# tritiled22_cr2354_xpe_reverse.net
KiCad netlist of a schematic drawn in EAGLE
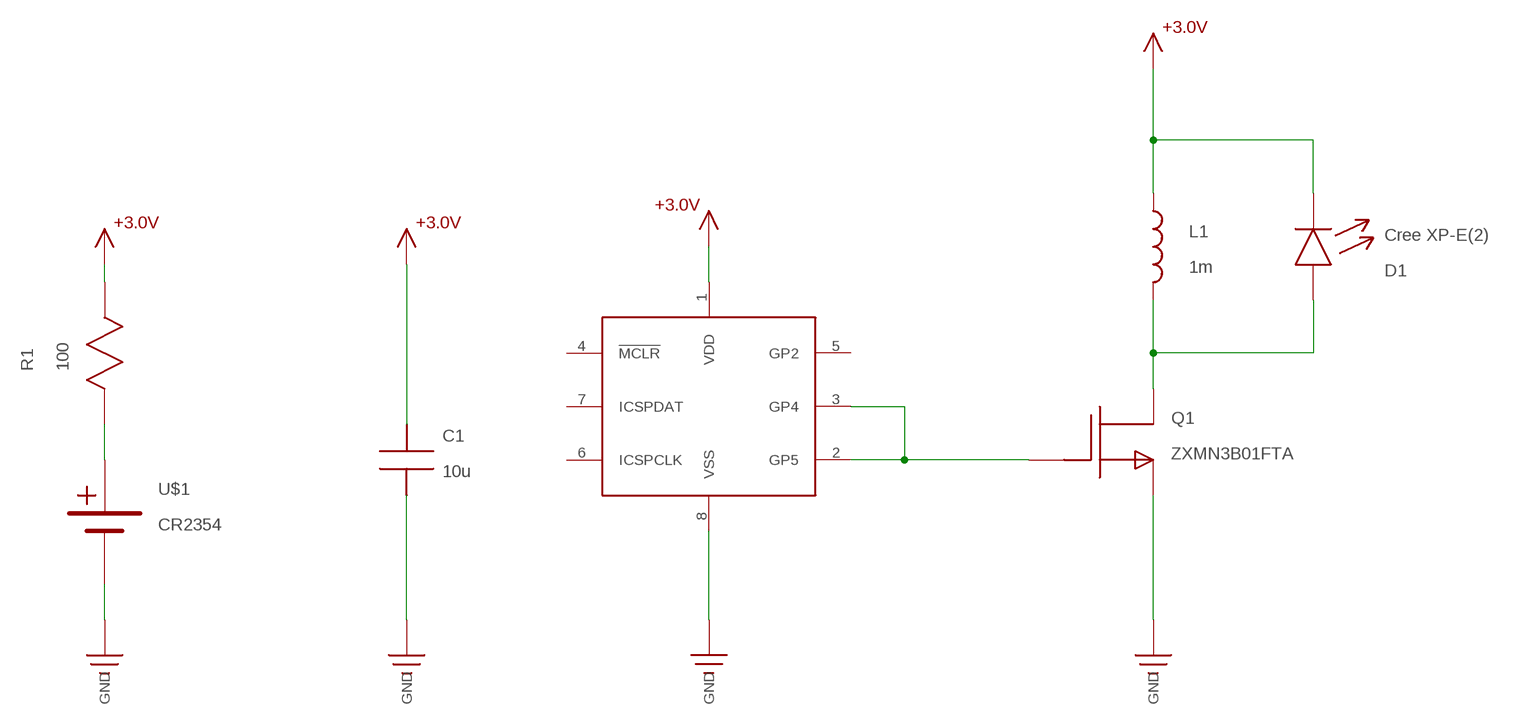
[diagram p0: schematic, sheet 1]

(export (version "E")
  (design (tool "Eeschema 10.0.6"))
  (components
    (comp (ref "C1")
      (value "10u")
      (footprint "eagle-import:1206")
      (libsource (lib "eagle-import") (part "C1206"))
    )
    (comp (ref "D1")
      (value "Cree XP-E(2)")
      (footprint "eagle-import:CREE_XPE_LED")
      (libsource (lib "eagle-import") (part "LEDCREE_XPE"))
    )
    (comp (ref "L1")
      (value "1m")
      (footprint "eagle-import:SRR6028_INDUCTOR")
      (libsource (lib "eagle-import") (part "SRR6028_INDUCTOR"))
    )
    (comp (ref "Q1")
      (value "ZXMN3B01FTA")
      (footprint "eagle-import:SOT-23")
      (libsource (lib "eagle-import") (part "ZXMN3B01FSOT23"))
    )
    (comp (ref "R1")
      (value "100")
      (footprint "eagle-import:R1206")
      (libsource (lib "eagle-import") (part "R1206"))
    )
    (comp (ref "U$1")
      (value "CR2354")
      (footprint "eagle-import:CR2354_TABBED")
      (libsource (lib "eagle-import") (part "CR2354_TABBED"))
    )
    (comp (ref "U1")
      (value "PIC12LF1571")
      (footprint "eagle-import:SOIC8")
      (libsource (lib "eagle-import") (part "PIC12LF1571"))
    )
  )
  (nets
    (net (code "1") (name "+3.0V") (class "Default")
      (node (ref "C1") (pin "P$1") (pinfunction "P$1_P$1") (pintype "bidirectional"))
      (node (ref "D1") (pin "C") (pinfunction "C_C") (pintype "bidirectional"))
      (node (ref "L1") (pin "P$1") (pinfunction "1_P$1") (pintype "passive"))
      (node (ref "R1") (pin "P$2") (pinfunction "P$2_P$2") (pintype "bidirectional"))
      (node (ref "U1") (pin "1") (pinfunction "VDD_1") (pintype "bidirectional"))
    )
    (net (code "2") (name "GND") (class "Default")
      (node (ref "C1") (pin "P$2") (pinfunction "P$2_P$2") (pintype "bidirectional"))
      (node (ref "Q1") (pin "2") (pinfunction "S_2") (pintype "bidirectional"))
      (node (ref "U$1") (pin "GND") (pinfunction "0V_GND") (pintype "power_in"))
      (node (ref "U1") (pin "8") (pinfunction "VSS_8") (pintype "bidirectional"))
    )
    (net (code "3") (name "Net-(L1-2)") (class "Default")
      (node (ref "D1") (pin "A") (pinfunction "A_A") (pintype "bidirectional"))
      (node (ref "L1") (pin "P$2") (pinfunction "2_P$2") (pintype "passive"))
      (node (ref "Q1") (pin "3") (pinfunction "D_3") (pintype "bidirectional"))
    )
    (net (code "4") (name "Net-(Q1-G)") (class "Default")
      (node (ref "Q1") (pin "1") (pinfunction "G_1") (pintype "bidirectional"))
      (node (ref "U1") (pin "2") (pinfunction "GP5_2") (pintype "bidirectional"))
      (node (ref "U1") (pin "3") (pinfunction "GP4_3") (pintype "bidirectional"))
    )
    (net (code "5") (name "Net-(U$1-+V)") (class "Default")
      (node (ref "R1") (pin "P$1") (pinfunction "P$1_P$1") (pintype "bidirectional"))
      (node (ref "U$1") (pin "+3V") (pinfunction "+V_+3V") (pintype "power_in"))
    )
    (net (code "6") (name "unconnected-(U1-GP2-Pad5)") (class "Default")
      (node (ref "U1") (pin "5") (pinfunction "GP2_5") (pintype "bidirectional"))
    )
    (net (code "7") (name "unconnected-(U1-ICSPCLK-Pad6)") (class "Default")
      (node (ref "U1") (pin "6") (pinfunction "ICSPCLK_6") (pintype "bidirectional"))
    )
    (net (code "8") (name "unconnected-(U1-ICSPDAT-Pad7)") (class "Default")
      (node (ref "U1") (pin "7") (pinfunction "ICSPDAT_7") (pintype "bidirectional"))
    )
    (net (code "9") (name "unconnected-(U1-~{MCLR}-Pad4)") (class "Default")
      (node (ref "U1") (pin "4") (pinfunction "~{MCLR}_4") (pintype "bidirectional"))
    )
  )
)
